# doorctl2.net
KiCad netlist of a schematic drawn in EAGLE
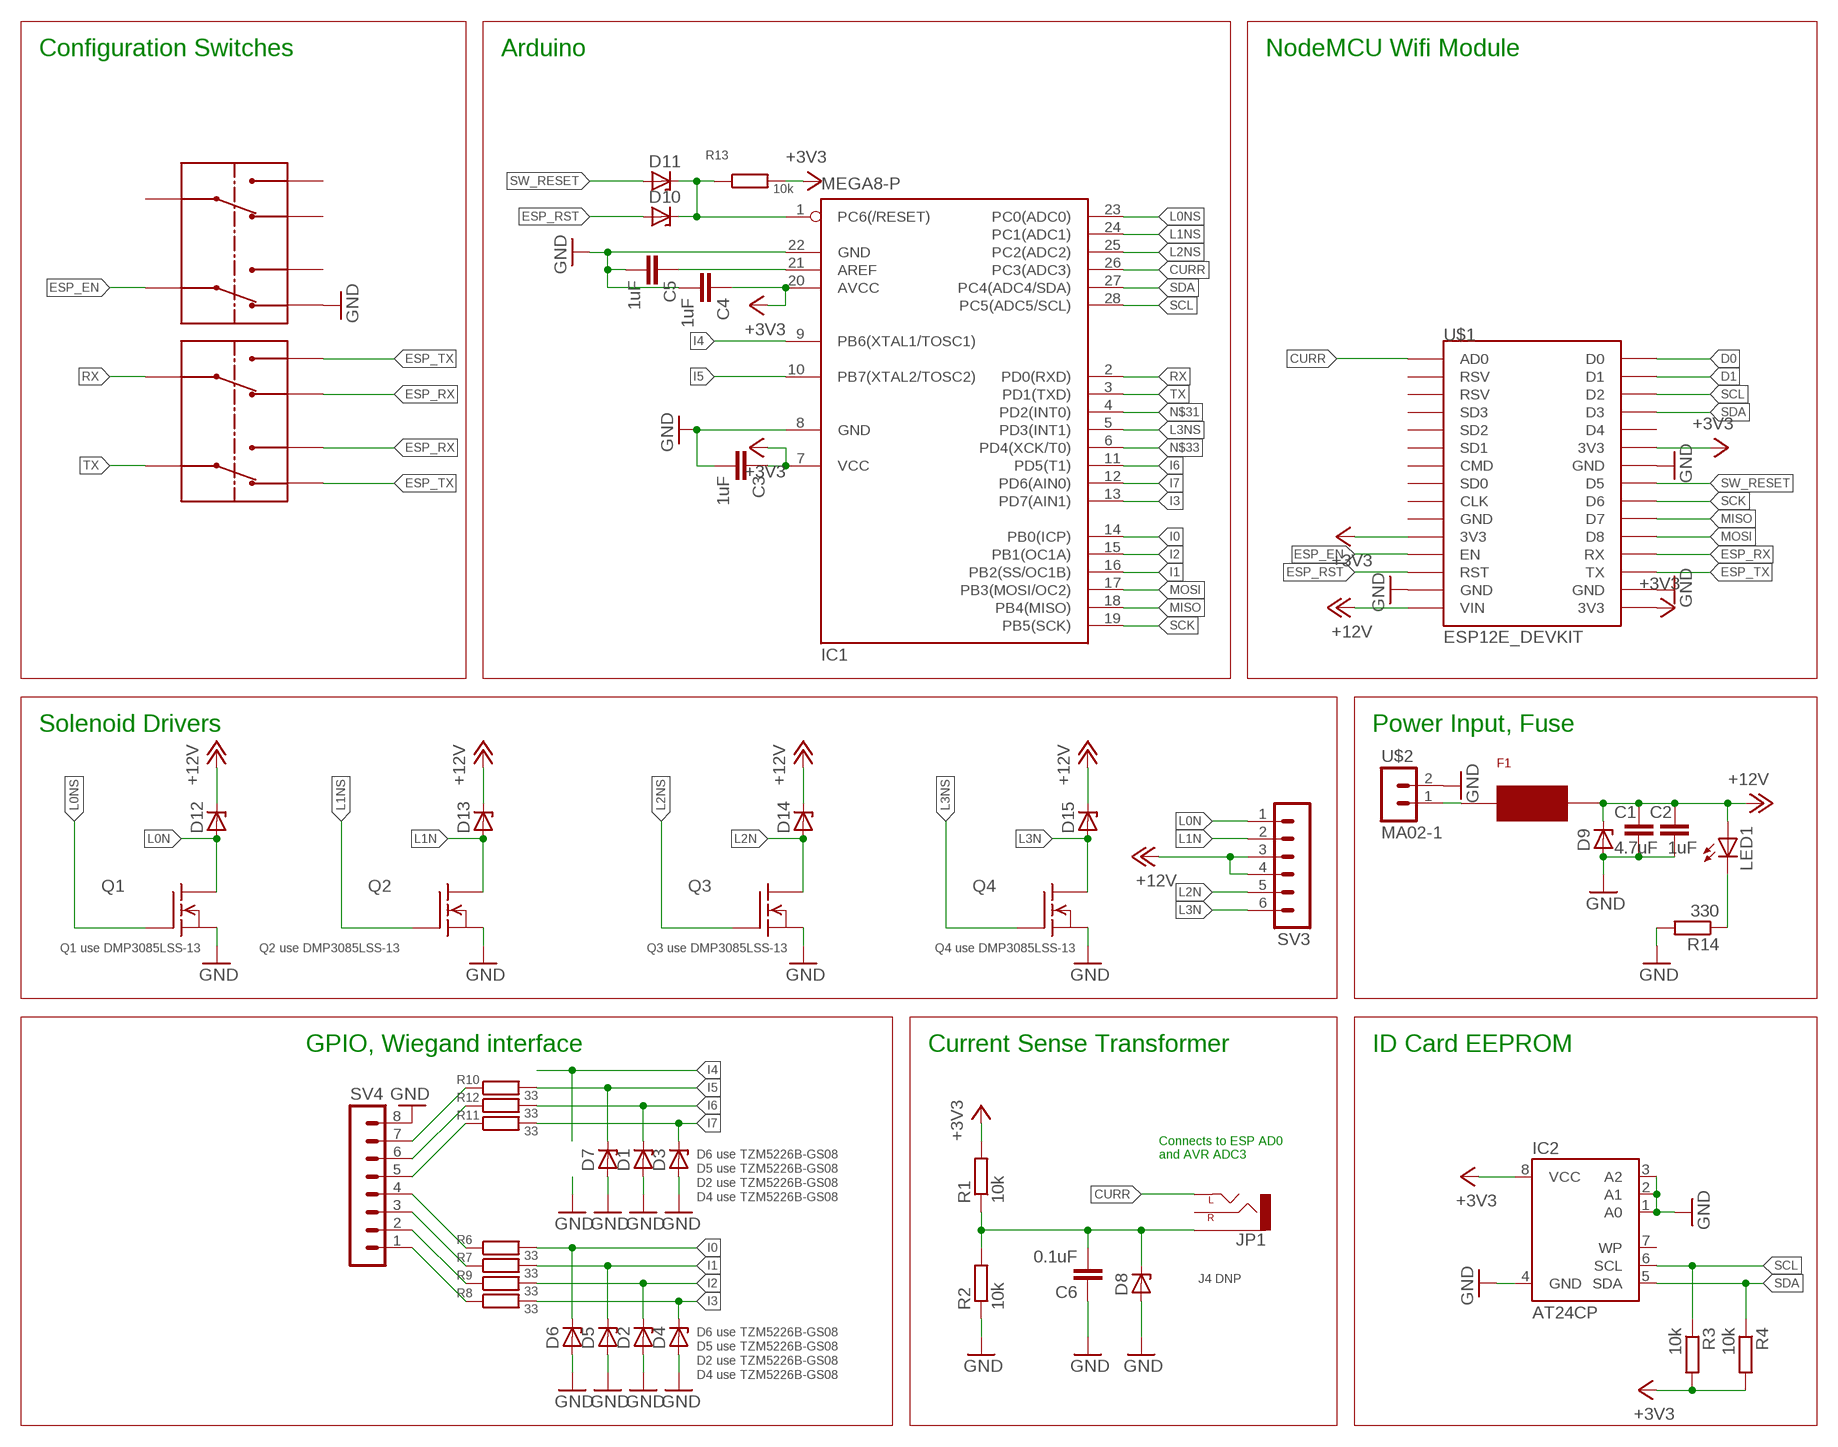
[diagram p0: schematic, sheet 1]

(export (version "E")
  (design (tool "Eeschema 10.0.6"))
  (components
    (comp (ref "C1")
      (value "4.7uF")
      (footprint "eagle-import:C0805")
      (libsource (lib "eagle-import") (part "C-EUC0805"))
    )
    (comp (ref "C2")
      (value "1uF")
      (footprint "eagle-import:C0805")
      (libsource (lib "eagle-import") (part "C-EUC0805"))
    )
    (comp (ref "C3")
      (value "1uF")
      (footprint "eagle-import:C0603")
      (libsource (lib "eagle-import") (part "C-EUC0603"))
    )
    (comp (ref "C4")
      (value "1uF")
      (footprint "eagle-import:C0603")
      (libsource (lib "eagle-import") (part "C-EUC0603"))
    )
    (comp (ref "C5")
      (value "1uF")
      (footprint "eagle-import:C0603")
      (libsource (lib "eagle-import") (part "C-EUC0603"))
    )
    (comp (ref "C6")
      (value "0.1uF")
      (footprint "eagle-import:C0603")
      (libsource (lib "eagle-import") (part "C-EUC0603"))
    )
    (comp (ref "D1")
      (value "ZENER-DIODESOD80C")
      (footprint "eagle-import:SOD80C")
      (libsource (lib "eagle-import") (part "ZENER-DIODESOD80C"))
    )
    (comp (ref "D2")
      (value "ZENER-DIODESOD80C")
      (footprint "eagle-import:SOD80C")
      (libsource (lib "eagle-import") (part "ZENER-DIODESOD80C"))
    )
    (comp (ref "D3")
      (value "ZENER-DIODESOD80C")
      (footprint "eagle-import:SOD80C")
      (libsource (lib "eagle-import") (part "ZENER-DIODESOD80C"))
    )
    (comp (ref "D4")
      (value "ZENER-DIODESOD80C")
      (footprint "eagle-import:SOD80C")
      (libsource (lib "eagle-import") (part "ZENER-DIODESOD80C"))
    )
    (comp (ref "D5")
      (value "ZENER-DIODESOD80C")
      (footprint "eagle-import:SOD80C")
      (libsource (lib "eagle-import") (part "ZENER-DIODESOD80C"))
    )
    (comp (ref "D6")
      (value "ZENER-DIODESOD80C")
      (footprint "eagle-import:SOD80C")
      (libsource (lib "eagle-import") (part "ZENER-DIODESOD80C"))
    )
    (comp (ref "D7")
      (value "ZENER-DIODESOD80C")
      (footprint "eagle-import:SOD80C")
      (libsource (lib "eagle-import") (part "ZENER-DIODESOD80C"))
    )
    (comp (ref "D8")
      (value "ZENER-DIODESOD80C")
      (footprint "eagle-import:SOD80C")
      (libsource (lib "eagle-import") (part "ZENER-DIODESOD80C"))
    )
    (comp (ref "D9")
      (value "ZENER-DIODESOD80C")
      (footprint "eagle-import:SOD80C")
      (libsource (lib "eagle-import") (part "ZENER-DIODESOD80C"))
    )
    (comp (ref "D10")
      (value "ZENER-DIODESOT23")
      (footprint "eagle-import:SOT23")
      (libsource (lib "eagle-import") (part "ZENER-DIODESOT23"))
    )
    (comp (ref "D11")
      (value "ZENER-DIODESOT23")
      (footprint "eagle-import:SOT23")
      (libsource (lib "eagle-import") (part "ZENER-DIODESOT23"))
    )
    (comp (ref "D12")
      (value "ZENER-DIODESOD80C")
      (footprint "eagle-import:SOD80C")
      (libsource (lib "eagle-import") (part "ZENER-DIODESOD80C"))
    )
    (comp (ref "D13")
      (value "ZENER-DIODESOD80C")
      (footprint "eagle-import:SOD80C")
      (libsource (lib "eagle-import") (part "ZENER-DIODESOD80C"))
    )
    (comp (ref "D14")
      (value "ZENER-DIODESOD80C")
      (footprint "eagle-import:SOD80C")
      (libsource (lib "eagle-import") (part "ZENER-DIODESOD80C"))
    )
    (comp (ref "D15")
      (value "ZENER-DIODESOD80C")
      (footprint "eagle-import:SOD80C")
      (libsource (lib "eagle-import") (part "ZENER-DIODESOD80C"))
    )
    (comp (ref "F1")
      (value "0154")
      (footprint "eagle-import:0154")
      (libsource (lib "eagle-import") (part "0154"))
    )
    (comp (ref "IC1")
      (value "MEGA8-P")
      (footprint "eagle-import:DIL28-3")
      (libsource (lib "eagle-import") (part "MEGA8-P"))
    )
    (comp (ref "IC2")
      (value "AT24CP")
      (footprint "eagle-import:DIL08")
      (fields (field (name "MPN") "AT24C1024BW-SH-B"))
      (libsource (lib "eagle-import") (part "AT24CP"))
    )
    (comp (ref "JP1")
      (value "AUDIO-JACKSMD2")
      (footprint "eagle-import:AUDIO-JACK-3.5MM-SMD")
      (libsource (lib "eagle-import") (part "AUDIO-JACKSMD2"))
    )
    (comp (ref "LED1")
      (value "LEDCHIP-LED0603")
      (footprint "eagle-import:CHIP-LED0603")
      (libsource (lib "eagle-import") (part "LEDCHIP-LED0603"))
    )
    (comp (ref "Q1")
      (value "FDS5680")
      (footprint "eagle-import:SO-8")
      (libsource (lib "eagle-import") (part "FDS5680"))
    )
    (comp (ref "Q2")
      (value "FDS5680")
      (footprint "eagle-import:SO-8")
      (libsource (lib "eagle-import") (part "FDS5680"))
    )
    (comp (ref "Q3")
      (value "FDS5680")
      (footprint "eagle-import:SO-8")
      (libsource (lib "eagle-import") (part "FDS5680"))
    )
    (comp (ref "Q4")
      (value "FDS5680")
      (footprint "eagle-import:SO-8")
      (libsource (lib "eagle-import") (part "FDS5680"))
    )
    (comp (ref "R1")
      (value "10k")
      (footprint "eagle-import:R0603")
      (libsource (lib "eagle-import") (part "R-EU_R0603"))
    )
    (comp (ref "R2")
      (value "10k")
      (footprint "eagle-import:R0603")
      (libsource (lib "eagle-import") (part "R-EU_R0603"))
    )
    (comp (ref "R3")
      (value "10k")
      (footprint "eagle-import:R0603")
      (libsource (lib "eagle-import") (part "R-EU_R0603"))
    )
    (comp (ref "R4")
      (value "10k")
      (footprint "eagle-import:R0603")
      (libsource (lib "eagle-import") (part "R-EU_R0603"))
    )
    (comp (ref "R6")
      (value "33")
      (footprint "eagle-import:R0603")
      (libsource (lib "eagle-import") (part "R-EU_R0603"))
    )
    (comp (ref "R7")
      (value "33")
      (footprint "eagle-import:R0603")
      (libsource (lib "eagle-import") (part "R-EU_R0603"))
    )
    (comp (ref "R8")
      (value "33")
      (footprint "eagle-import:R0603")
      (libsource (lib "eagle-import") (part "R-EU_R0603"))
    )
    (comp (ref "R9")
      (value "33")
      (footprint "eagle-import:R0603")
      (libsource (lib "eagle-import") (part "R-EU_R0603"))
    )
    (comp (ref "R10")
      (value "33")
      (footprint "eagle-import:R0603")
      (libsource (lib "eagle-import") (part "R-EU_R0603"))
    )
    (comp (ref "R11")
      (value "33")
      (footprint "eagle-import:R0603")
      (libsource (lib "eagle-import") (part "R-EU_R0603"))
    )
    (comp (ref "R12")
      (value "33")
      (footprint "eagle-import:R0603")
      (libsource (lib "eagle-import") (part "R-EU_R0603"))
    )
    (comp (ref "R13")
      (value "10k")
      (footprint "eagle-import:R0603")
      (libsource (lib "eagle-import") (part "R-EU_R0603"))
    )
    (comp (ref "R14")
      (value "330")
      (footprint "eagle-import:R0603")
      (libsource (lib "eagle-import") (part "R-EU_R0603"))
    )
    (comp (ref "SV3")
      (value "MA06-1")
      (footprint "eagle-import:MA06-1")
      (libsource (lib "eagle-import") (part "MA06-1"))
    )
    (comp (ref "SV4")
      (value "MA08-1")
      (footprint "eagle-import:MA08-1")
      (libsource (lib "eagle-import") (part "MA08-1"))
    )
    (comp (ref "SW1")
      (value "L202011MS02Q")
      (footprint "eagle-import:SMT")
      (libsource (lib "eagle-import") (part "L202011MS02Q"))
    )
    (comp (ref "SW2")
      (value "L202011MS02Q")
      (footprint "eagle-import:SMT")
      (libsource (lib "eagle-import") (part "L202011MS02Q"))
    )
    (comp (ref "U$1")
      (value "ESP12E_DEVKIT")
      (footprint "eagle-import:ESP12E_DEVKIT")
      (libsource (lib "eagle-import") (part "ESP12E_DEVKIT"))
    )
    (comp (ref "U$2")
      (value "MA02-1")
      (footprint "eagle-import:MA02-1")
      (libsource (lib "eagle-import") (part "MA02-1"))
    )
  )
  (nets
    (net (code "1") (name "+3V3") (class "Default")
      (node (ref "C3") (pin "1") (pinfunction "1_1") (pintype "passive"))
      (node (ref "C4") (pin "1") (pinfunction "1_1") (pintype "passive"))
      (node (ref "IC1") (pin "20") (pinfunction "AVCC_20") (pintype "power_in"))
      (node (ref "IC1") (pin "7") (pinfunction "VCC_7") (pintype "power_in"))
      (node (ref "IC2") (pin "8") (pinfunction "VCC_8") (pintype "power_in"))
      (node (ref "R1") (pin "2") (pinfunction "2_2") (pintype "passive"))
      (node (ref "R13") (pin "2") (pinfunction "2_2") (pintype "passive"))
      (node (ref "R3") (pin "2") (pinfunction "2_2") (pintype "passive"))
      (node (ref "R4") (pin "2") (pinfunction "2_2") (pintype "passive"))
      (node (ref "U$1") (pin "3V3@0") (pinfunction "3V3_3V3@0") (pintype "bidirectional"))
      (node (ref "U$1") (pin "3V3@1") (pinfunction "3V3_3V3@1") (pintype "bidirectional"))
      (node (ref "U$1") (pin "3V3@2") (pinfunction "3V3_3V3@2") (pintype "bidirectional"))
    )
    (net (code "2") (name "+12V") (class "Default")
      (node (ref "C1") (pin "1") (pinfunction "1_1") (pintype "passive"))
      (node (ref "C2") (pin "1") (pinfunction "1_1") (pintype "passive"))
      (node (ref "D12") (pin "C") (pinfunction "C_C") (pintype "passive"))
      (node (ref "D13") (pin "C") (pinfunction "C_C") (pintype "passive"))
      (node (ref "D14") (pin "C") (pinfunction "C_C") (pintype "passive"))
      (node (ref "D15") (pin "C") (pinfunction "C_C") (pintype "passive"))
      (node (ref "D9") (pin "C") (pinfunction "C_C") (pintype "passive"))
      (node (ref "F1") (pin "2") (pinfunction "P$2_2") (pintype "bidirectional"))
      (node (ref "LED1") (pin "A") (pinfunction "A_A") (pintype "passive"))
      (node (ref "SV3") (pin "3") (pinfunction "3_3") (pintype "passive"))
      (node (ref "SV3") (pin "4") (pinfunction "4_4") (pintype "passive"))
      (node (ref "U$1") (pin "VIN") (pinfunction "VIN_VIN") (pintype "bidirectional"))
    )
    (net (code "3") (name "CURR") (class "Default")
      (node (ref "IC1") (pin "26") (pinfunction "PC3(ADC3)_26") (pintype "bidirectional"))
      (node (ref "JP1") (pin "TIP") (pinfunction "LEFT_TIP") (pintype "bidirectional"))
      (node (ref "U$1") (pin "AD0") (pinfunction "AD0_AD0") (pintype "bidirectional"))
    )
    (net (code "4") (name "D0") (class "Default")
      (node (ref "U$1") (pin "D0") (pinfunction "D0_D0") (pintype "bidirectional"))
    )
    (net (code "5") (name "D1") (class "Default")
      (node (ref "U$1") (pin "D1") (pinfunction "D1_D1") (pintype "bidirectional"))
    )
    (net (code "6") (name "ESP_EN") (class "Default")
      (node (ref "SW1") (pin "A") (pinfunction "A_A") (pintype "bidirectional"))
      (node (ref "U$1") (pin "EN") (pinfunction "EN_EN") (pintype "bidirectional"))
    )
    (net (code "7") (name "ESP_RST") (class "Default")
      (node (ref "D10") (pin "1") (pinfunction "A_1") (pintype "passive"))
      (node (ref "U$1") (pin "RST") (pinfunction "RST_RST") (pintype "bidirectional"))
    )
    (net (code "8") (name "ESP_RX") (class "Default")
      (node (ref "SW2") (pin "A1") (pinfunction "A1_A1") (pintype "bidirectional"))
      (node (ref "SW2") (pin "B2") (pinfunction "B2_B2") (pintype "bidirectional"))
      (node (ref "U$1") (pin "RX") (pinfunction "RX_RX") (pintype "bidirectional"))
    )
    (net (code "9") (name "ESP_TX") (class "Default")
      (node (ref "SW2") (pin "A2") (pinfunction "A2_A2") (pintype "bidirectional"))
      (node (ref "SW2") (pin "B1") (pinfunction "B1_B1") (pintype "bidirectional"))
      (node (ref "U$1") (pin "TX") (pinfunction "TX_TX") (pintype "bidirectional"))
    )
    (net (code "10") (name "GND") (class "Default")
      (node (ref "C1") (pin "2") (pinfunction "2_2") (pintype "passive"))
      (node (ref "C2") (pin "2") (pinfunction "2_2") (pintype "passive"))
      (node (ref "C3") (pin "2") (pinfunction "2_2") (pintype "passive"))
      (node (ref "C4") (pin "2") (pinfunction "2_2") (pintype "passive"))
      (node (ref "C5") (pin "2") (pinfunction "2_2") (pintype "passive"))
      (node (ref "C6") (pin "1") (pinfunction "1_1") (pintype "passive"))
      (node (ref "D1") (pin "A") (pinfunction "A_A") (pintype "passive"))
      (node (ref "D2") (pin "A") (pinfunction "A_A") (pintype "passive"))
      (node (ref "D3") (pin "A") (pinfunction "A_A") (pintype "passive"))
      (node (ref "D4") (pin "A") (pinfunction "A_A") (pintype "passive"))
      (node (ref "D5") (pin "A") (pinfunction "A_A") (pintype "passive"))
      (node (ref "D6") (pin "A") (pinfunction "A_A") (pintype "passive"))
      (node (ref "D7") (pin "A") (pinfunction "A_A") (pintype "passive"))
      (node (ref "D8") (pin "A") (pinfunction "A_A") (pintype "passive"))
      (node (ref "D9") (pin "A") (pinfunction "A_A") (pintype "passive"))
      (node (ref "IC1") (pin "22") (pinfunction "GND_22") (pintype "power_in"))
      (node (ref "IC1") (pin "8") (pinfunction "GND_8") (pintype "power_in"))
      (node (ref "IC2") (pin "1") (pinfunction "A0_1") (pintype "input"))
      (node (ref "IC2") (pin "2") (pinfunction "A1_2") (pintype "input"))
      (node (ref "IC2") (pin "3") (pinfunction "A2_3") (pintype "input"))
      (node (ref "IC2") (pin "4") (pinfunction "GND_4") (pintype "power_in"))
      (node (ref "Q1") (pin "1") (pinfunction "S_1") (pintype "passive"))
      (node (ref "Q1") (pin "2") (pinfunction "S_2") (pintype "passive"))
      (node (ref "Q1") (pin "3") (pinfunction "S_3") (pintype "passive"))
      (node (ref "Q2") (pin "1") (pinfunction "S_1") (pintype "passive"))
      (node (ref "Q2") (pin "2") (pinfunction "S_2") (pintype "passive"))
      (node (ref "Q2") (pin "3") (pinfunction "S_3") (pintype "passive"))
      (node (ref "Q3") (pin "1") (pinfunction "S_1") (pintype "passive"))
      (node (ref "Q3") (pin "2") (pinfunction "S_2") (pintype "passive"))
      (node (ref "Q3") (pin "3") (pinfunction "S_3") (pintype "passive"))
      (node (ref "Q4") (pin "1") (pinfunction "S_1") (pintype "passive"))
      (node (ref "Q4") (pin "2") (pinfunction "S_2") (pintype "passive"))
      (node (ref "Q4") (pin "3") (pinfunction "S_3") (pintype "passive"))
      (node (ref "R14") (pin "2") (pinfunction "2_2") (pintype "passive"))
      (node (ref "R2") (pin "1") (pinfunction "1_1") (pintype "passive"))
      (node (ref "SV4") (pin "8") (pinfunction "8_8") (pintype "passive"))
      (node (ref "SW1") (pin "A2") (pinfunction "A2_A2") (pintype "bidirectional"))
      (node (ref "U$1") (pin "GND@1") (pinfunction "GND_GND@1") (pintype "bidirectional"))
      (node (ref "U$1") (pin "GND@2") (pinfunction "GND_GND@2") (pintype "bidirectional"))
      (node (ref "U$1") (pin "GND@3") (pinfunction "GND_GND@3") (pintype "bidirectional"))
      (node (ref "U$2") (pin "2") (pinfunction "2_2") (pintype "passive"))
    )
    (net (code "11") (name "I0") (class "Default")
      (node (ref "D6") (pin "C") (pinfunction "C_C") (pintype "passive"))
      (node (ref "IC1") (pin "14") (pinfunction "PB0(ICP)_14") (pintype "bidirectional"))
      (node (ref "R6") (pin "2") (pinfunction "2_2") (pintype "passive"))
    )
    (net (code "12") (name "I1") (class "Default")
      (node (ref "D5") (pin "C") (pinfunction "C_C") (pintype "passive"))
      (node (ref "IC1") (pin "16") (pinfunction "PB2(SS/OC1B)_16") (pintype "bidirectional"))
      (node (ref "R7") (pin "2") (pinfunction "2_2") (pintype "passive"))
    )
    (net (code "13") (name "I2") (class "Default")
      (node (ref "D2") (pin "C") (pinfunction "C_C") (pintype "passive"))
      (node (ref "IC1") (pin "15") (pinfunction "PB1(OC1A)_15") (pintype "bidirectional"))
      (node (ref "R8") (pin "2") (pinfunction "2_2") (pintype "passive"))
    )
    (net (code "14") (name "I3") (class "Default")
      (node (ref "D4") (pin "C") (pinfunction "C_C") (pintype "passive"))
      (node (ref "IC1") (pin "13") (pinfunction "PD7(AIN1)_13") (pintype "bidirectional"))
      (node (ref "R9") (pin "2") (pinfunction "2_2") (pintype "passive"))
    )
    (net (code "15") (name "I4") (class "Default")
      (node (ref "IC1") (pin "9") (pinfunction "PB6(XTAL1/TOSC1)_9") (pintype "bidirectional"))
    )
    (net (code "16") (name "I5") (class "Default")
      (node (ref "D7") (pin "C") (pinfunction "C_C") (pintype "passive"))
      (node (ref "IC1") (pin "10") (pinfunction "PB7(XTAL2/TOSC2)_10") (pintype "bidirectional"))
      (node (ref "R10") (pin "2") (pinfunction "2_2") (pintype "passive"))
    )
    (net (code "17") (name "I6") (class "Default")
      (node (ref "D1") (pin "C") (pinfunction "C_C") (pintype "passive"))
      (node (ref "IC1") (pin "11") (pinfunction "PD5(T1)_11") (pintype "bidirectional"))
      (node (ref "R11") (pin "2") (pinfunction "2_2") (pintype "passive"))
    )
    (net (code "18") (name "I7") (class "Default")
      (node (ref "D3") (pin "C") (pinfunction "C_C") (pintype "passive"))
      (node (ref "IC1") (pin "12") (pinfunction "PD6(AIN0)_12") (pintype "bidirectional"))
      (node (ref "R12") (pin "2") (pinfunction "2_2") (pintype "passive"))
    )
    (net (code "19") (name "L0N") (class "Default")
      (node (ref "D12") (pin "A") (pinfunction "A_A") (pintype "passive"))
      (node (ref "Q1") (pin "5") (pinfunction "D_5") (pintype "passive"))
      (node (ref "Q1") (pin "6") (pinfunction "D_6") (pintype "passive"))
      (node (ref "Q1") (pin "7") (pinfunction "D_7") (pintype "passive"))
      (node (ref "Q1") (pin "8") (pinfunction "D_8") (pintype "passive"))
      (node (ref "SV3") (pin "1") (pinfunction "1_1") (pintype "passive"))
    )
    (net (code "20") (name "L0NS") (class "Default")
      (node (ref "IC1") (pin "23") (pinfunction "PC0(ADC0)_23") (pintype "bidirectional"))
      (node (ref "Q1") (pin "4") (pinfunction "G_4") (pintype "passive"))
    )
    (net (code "21") (name "L1N") (class "Default")
      (node (ref "D13") (pin "A") (pinfunction "A_A") (pintype "passive"))
      (node (ref "Q2") (pin "5") (pinfunction "D_5") (pintype "passive"))
      (node (ref "Q2") (pin "6") (pinfunction "D_6") (pintype "passive"))
      (node (ref "Q2") (pin "7") (pinfunction "D_7") (pintype "passive"))
      (node (ref "Q2") (pin "8") (pinfunction "D_8") (pintype "passive"))
      (node (ref "SV3") (pin "2") (pinfunction "2_2") (pintype "passive"))
    )
    (net (code "22") (name "L1NS") (class "Default")
      (node (ref "IC1") (pin "24") (pinfunction "PC1(ADC1)_24") (pintype "bidirectional"))
      (node (ref "Q2") (pin "4") (pinfunction "G_4") (pintype "passive"))
    )
    (net (code "23") (name "L2N") (class "Default")
      (node (ref "D14") (pin "A") (pinfunction "A_A") (pintype "passive"))
      (node (ref "Q3") (pin "5") (pinfunction "D_5") (pintype "passive"))
      (node (ref "Q3") (pin "6") (pinfunction "D_6") (pintype "passive"))
      (node (ref "Q3") (pin "7") (pinfunction "D_7") (pintype "passive"))
      (node (ref "Q3") (pin "8") (pinfunction "D_8") (pintype "passive"))
      (node (ref "SV3") (pin "5") (pinfunction "5_5") (pintype "passive"))
    )
    (net (code "24") (name "L2NS") (class "Default")
      (node (ref "IC1") (pin "25") (pinfunction "PC2(ADC2)_25") (pintype "bidirectional"))
      (node (ref "Q3") (pin "4") (pinfunction "G_4") (pintype "passive"))
    )
    (net (code "25") (name "L3N") (class "Default")
      (node (ref "D15") (pin "A") (pinfunction "A_A") (pintype "passive"))
      (node (ref "Q4") (pin "5") (pinfunction "D_5") (pintype "passive"))
      (node (ref "Q4") (pin "6") (pinfunction "D_6") (pintype "passive"))
      (node (ref "Q4") (pin "7") (pinfunction "D_7") (pintype "passive"))
      (node (ref "Q4") (pin "8") (pinfunction "D_8") (pintype "passive"))
      (node (ref "SV3") (pin "6") (pinfunction "6_6") (pintype "passive"))
    )
    (net (code "26") (name "L3NS") (class "Default")
      (node (ref "IC1") (pin "5") (pinfunction "PD3(INT1)_5") (pintype "bidirectional"))
      (node (ref "Q4") (pin "4") (pinfunction "G_4") (pintype "passive"))
    )
    (net (code "27") (name "MISO") (class "Default")
      (node (ref "IC1") (pin "18") (pinfunction "PB4(MISO)_18") (pintype "bidirectional"))
      (node (ref "U$1") (pin "D7") (pinfunction "D7_D7") (pintype "bidirectional"))
    )
    (net (code "28") (name "MOSI") (class "Default")
      (node (ref "IC1") (pin "17") (pinfunction "PB3(MOSI/OC2)_17") (pintype "bidirectional"))
      (node (ref "U$1") (pin "D8") (pinfunction "D8_D8") (pintype "bidirectional"))
    )
    (net (code "29") (name "N$31") (class "Default")
      (node (ref "IC1") (pin "4") (pinfunction "PD2(INT0)_4") (pintype "bidirectional"))
    )
    (net (code "30") (name "N$33") (class "Default")
      (node (ref "IC1") (pin "6") (pinfunction "PD4(XCK/T0)_6") (pintype "bidirectional"))
    )
    (net (code "31") (name "Net-(C6-Pad2)") (class "Default")
      (node (ref "C6") (pin "2") (pinfunction "2_2") (pintype "passive"))
      (node (ref "D8") (pin "C") (pinfunction "C_C") (pintype "passive"))
      (node (ref "JP1") (pin "SLEEVE") (pinfunction "SLEEVE_SLEEVE") (pintype "bidirectional"))
      (node (ref "R1") (pin "1") (pinfunction "1_1") (pintype "passive"))
      (node (ref "R2") (pin "2") (pinfunction "2_2") (pintype "passive"))
    )
    (net (code "32") (name "Net-(D10-C)") (class "Default")
      (node (ref "D10") (pin "3") (pinfunction "C_3") (pintype "passive"))
      (node (ref "D11") (pin "3") (pinfunction "C_3") (pintype "passive"))
      (node (ref "IC1") (pin "1") (pinfunction "PC6(/RESET)_1") (pintype "bidirectional"))
      (node (ref "R13") (pin "1") (pinfunction "1_1") (pintype "passive"))
    )
    (net (code "33") (name "Net-(F1-P$1)") (class "Default")
      (node (ref "F1") (pin "1") (pinfunction "P$1_1") (pintype "bidirectional"))
      (node (ref "U$2") (pin "1") (pinfunction "1_1") (pintype "passive"))
    )
    (net (code "34") (name "Net-(IC1-AREF)") (class "Default")
      (node (ref "C5") (pin "1") (pinfunction "1_1") (pintype "passive"))
      (node (ref "IC1") (pin "21") (pinfunction "AREF_21") (pintype "passive"))
    )
    (net (code "35") (name "Net-(LED1-PadC)") (class "Default")
      (node (ref "LED1") (pin "C") (pinfunction "C_C") (pintype "passive"))
      (node (ref "R14") (pin "1") (pinfunction "1_1") (pintype "passive"))
    )
    (net (code "36") (name "Net-(R6-Pad1)") (class "Default")
      (node (ref "R6") (pin "1") (pinfunction "1_1") (pintype "passive"))
      (node (ref "SV4") (pin "4") (pinfunction "4_4") (pintype "passive"))
    )
    (net (code "37") (name "Net-(R7-Pad1)") (class "Default")
      (node (ref "R7") (pin "1") (pinfunction "1_1") (pintype "passive"))
      (node (ref "SV4") (pin "3") (pinfunction "3_3") (pintype "passive"))
    )
    (net (code "38") (name "Net-(R8-Pad1)") (class "Default")
      (node (ref "R8") (pin "1") (pinfunction "1_1") (pintype "passive"))
      (node (ref "SV4") (pin "2") (pinfunction "2_2") (pintype "passive"))
    )
    (net (code "39") (name "Net-(R9-Pad1)") (class "Default")
      (node (ref "R9") (pin "1") (pinfunction "1_1") (pintype "passive"))
      (node (ref "SV4") (pin "1") (pinfunction "1_1") (pintype "passive"))
    )
    (net (code "40") (name "Net-(R10-Pad1)") (class "Default")
      (node (ref "R10") (pin "1") (pinfunction "1_1") (pintype "passive"))
      (node (ref "SV4") (pin "7") (pinfunction "7_7") (pintype "passive"))
    )
    (net (code "41") (name "Net-(R11-Pad1)") (class "Default")
      (node (ref "R11") (pin "1") (pinfunction "1_1") (pintype "passive"))
      (node (ref "SV4") (pin "6") (pinfunction "6_6") (pintype "passive"))
    )
    (net (code "42") (name "Net-(R12-Pad1)") (class "Default")
      (node (ref "R12") (pin "1") (pinfunction "1_1") (pintype "passive"))
      (node (ref "SV4") (pin "5") (pinfunction "5_5") (pintype "passive"))
    )
    (net (code "43") (name "RX") (class "Default")
      (node (ref "IC1") (pin "2") (pinfunction "PD0(RXD)_2") (pintype "bidirectional"))
      (node (ref "SW2") (pin "B") (pinfunction "B_B") (pintype "bidirectional"))
    )
    (net (code "44") (name "SCK") (class "Default")
      (node (ref "IC1") (pin "19") (pinfunction "PB5(SCK)_19") (pintype "bidirectional"))
      (node (ref "U$1") (pin "D6") (pinfunction "D6_D6") (pintype "bidirectional"))
    )
    (net (code "45") (name "SCL") (class "Default")
      (node (ref "IC1") (pin "28") (pinfunction "PC5(ADC5/SCL)_28") (pintype "bidirectional"))
      (node (ref "IC2") (pin "6") (pinfunction "SCL_6") (pintype "bidirectional"))
      (node (ref "R3") (pin "1") (pinfunction "1_1") (pintype "passive"))
      (node (ref "U$1") (pin "D2") (pinfunction "D2_D2") (pintype "bidirectional"))
    )
    (net (code "46") (name "SDA") (class "Default")
      (node (ref "IC1") (pin "27") (pinfunction "PC4(ADC4/SDA)_27") (pintype "bidirectional"))
      (node (ref "IC2") (pin "5") (pinfunction "SDA_5") (pintype "bidirectional"))
      (node (ref "R4") (pin "1") (pinfunction "1_1") (pintype "passive"))
      (node (ref "U$1") (pin "D3") (pinfunction "D3_D3") (pintype "bidirectional"))
    )
    (net (code "47") (name "SW_RESET") (class "Default")
      (node (ref "D11") (pin "1") (pinfunction "A_1") (pintype "passive"))
      (node (ref "U$1") (pin "D5") (pinfunction "D5_D5") (pintype "bidirectional"))
    )
    (net (code "48") (name "TX") (class "Default")
      (node (ref "IC1") (pin "3") (pinfunction "PD1(TXD)_3") (pintype "bidirectional"))
      (node (ref "SW2") (pin "A") (pinfunction "A_A") (pintype "bidirectional"))
    )
    (net (code "49") (name "unconnected-(IC2-WP-Pad7)") (class "Default")
      (node (ref "IC2") (pin "7") (pinfunction "WP_7") (pintype "input"))
    )
    (net (code "50") (name "unconnected-(JP1-RIGHT-PadRING)") (class "Default")
      (node (ref "JP1") (pin "RING") (pinfunction "RIGHT_RING") (pintype "bidirectional"))
    )
    (net (code "51") (name "unconnected-(SW1-PadA1)") (class "Default")
      (node (ref "SW1") (pin "A1") (pinfunction "A1_A1") (pintype "bidirectional"))
    )
    (net (code "52") (name "unconnected-(SW1-PadB)") (class "Default")
      (node (ref "SW1") (pin "B") (pinfunction "B_B") (pintype "bidirectional"))
    )
    (net (code "53") (name "unconnected-(SW1-PadB1)") (class "Default")
      (node (ref "SW1") (pin "B1") (pinfunction "B1_B1") (pintype "bidirectional"))
    )
    (net (code "54") (name "unconnected-(SW1-PadB2)") (class "Default")
      (node (ref "SW1") (pin "B2") (pinfunction "B2_B2") (pintype "bidirectional"))
    )
    (net (code "55") (name "unconnected-(U$1-GND-PadGND@0)") (class "Default")
      (node (ref "U$1") (pin "GND@0") (pinfunction "GND_GND@0") (pintype "bidirectional"))
    )
    (net (code "56") (name "unconnected-(U$1-PadCLK)") (class "Default")
      (node (ref "U$1") (pin "CLK") (pinfunction "CLK_CLK") (pintype "bidirectional"))
    )
    (net (code "57") (name "unconnected-(U$1-PadCMD)") (class "Default")
      (node (ref "U$1") (pin "CMD") (pinfunction "CMD_CMD") (pintype "bidirectional"))
    )
    (net (code "58") (name "unconnected-(U$1-PadD4)") (class "Default")
      (node (ref "U$1") (pin "D4") (pinfunction "D4_D4") (pintype "bidirectional"))
    )
    (net (code "59") (name "unconnected-(U$1-PadSD0)") (class "Default")
      (node (ref "U$1") (pin "SD0") (pinfunction "SD0_SD0") (pintype "bidirectional"))
    )
    (net (code "60") (name "unconnected-(U$1-PadSD1)") (class "Default")
      (node (ref "U$1") (pin "SD1") (pinfunction "SD1_SD1") (pintype "bidirectional"))
    )
    (net (code "61") (name "unconnected-(U$1-PadSD2)") (class "Default")
      (node (ref "U$1") (pin "SD2") (pinfunction "SD2_SD2") (pintype "bidirectional"))
    )
    (net (code "62") (name "unconnected-(U$1-PadSD3)") (class "Default")
      (node (ref "U$1") (pin "SD3") (pinfunction "SD3_SD3") (pintype "bidirectional"))
    )
    (net (code "63") (name "unconnected-(U$1-RSV-PadRSV@0)") (class "Default")
      (node (ref "U$1") (pin "RSV@0") (pinfunction "RSV_RSV@0") (pintype "bidirectional"))
    )
    (net (code "64") (name "unconnected-(U$1-RSV-PadRSV@1)") (class "Default")
      (node (ref "U$1") (pin "RSV@1") (pinfunction "RSV_RSV@1") (pintype "bidirectional"))
    )
  )
)
